# BaseNode.net
KiCad netlist of a schematic drawn in Altium Designer
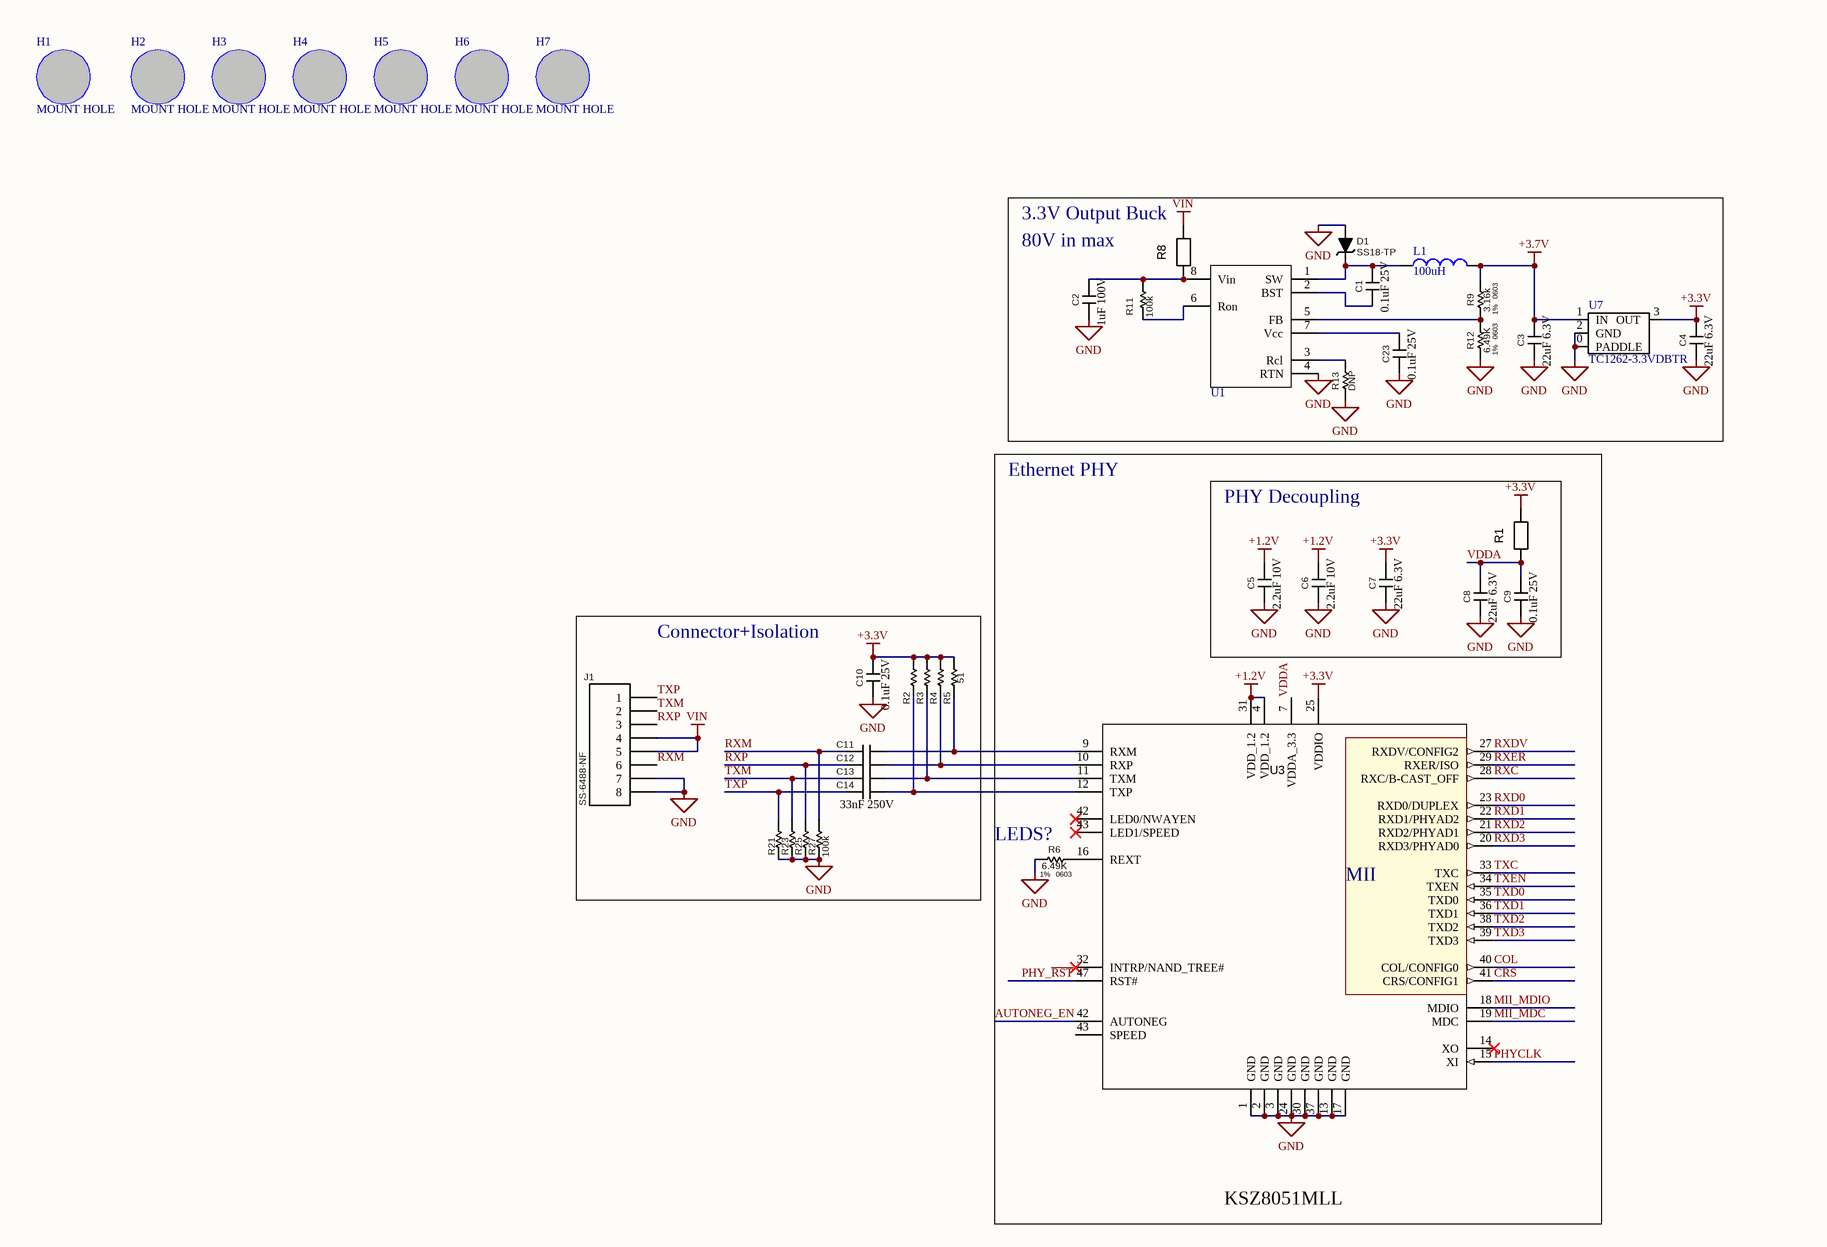
[diagram p0: BaseNode.SchDoc, top left]
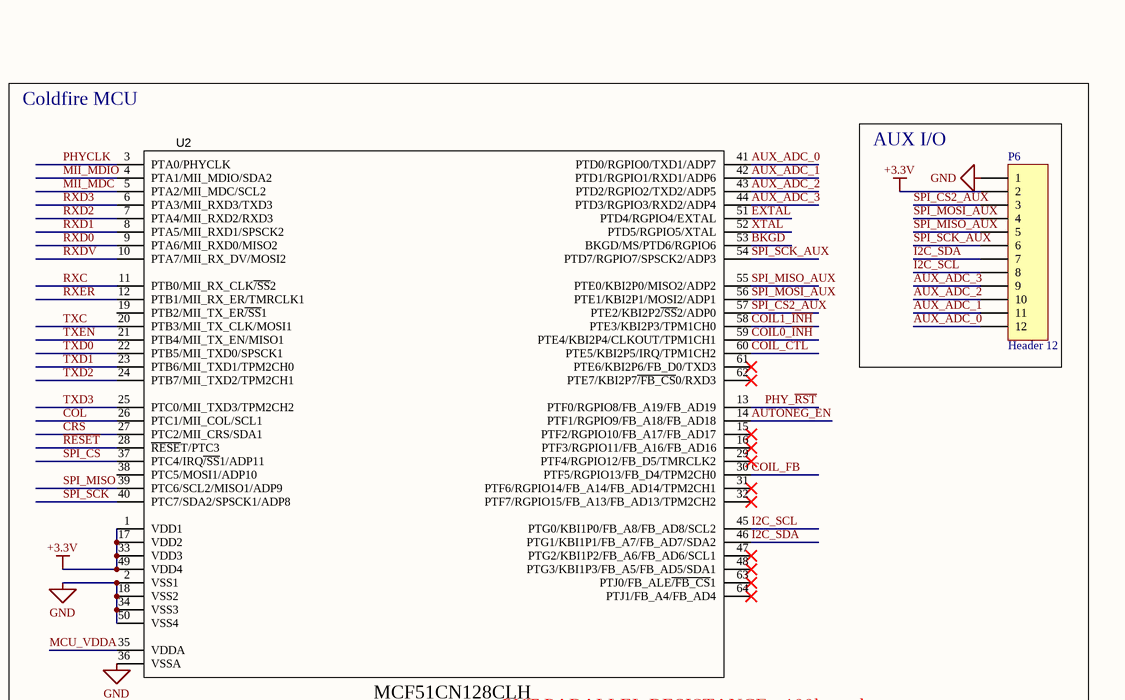
[diagram p1: BaseNode.SchDoc, top right]
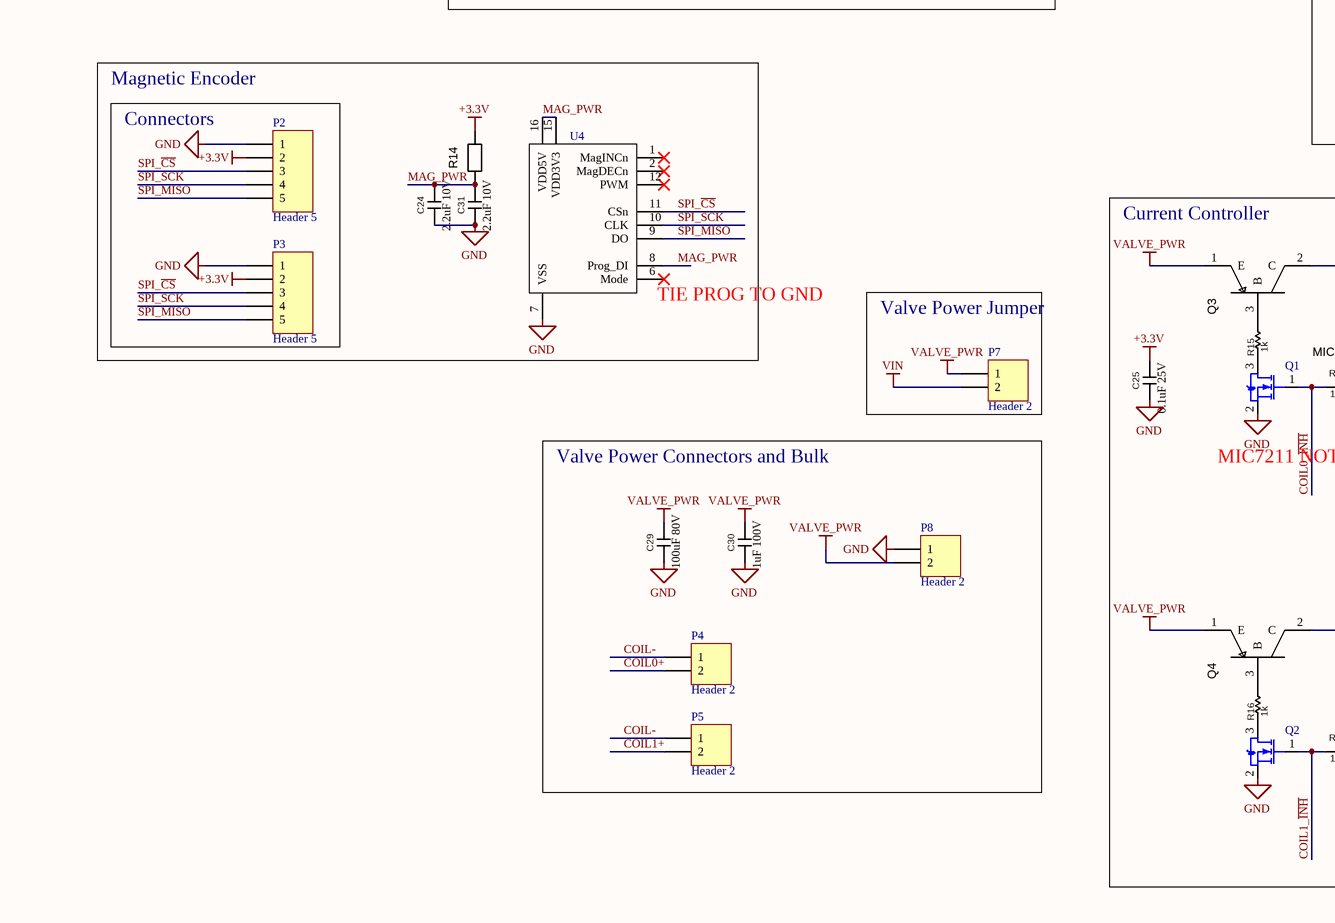
[diagram p2: BaseNode.SchDoc, bottom left]
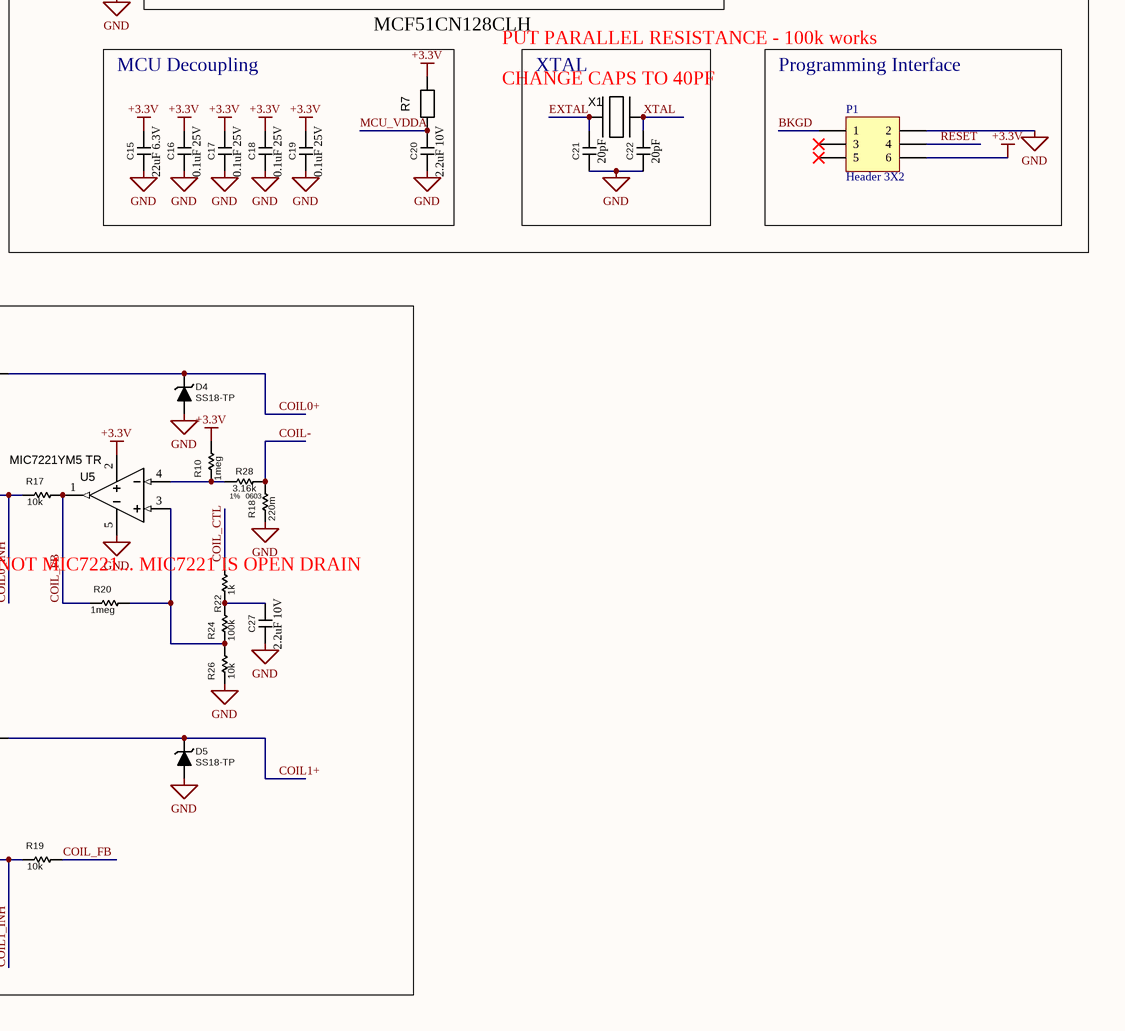
[diagram p3: BaseNode.SchDoc, bottom right]

(export (version "E")
  (design (tool "Eeschema 10.0.6"))
  (components
    (comp (ref "C1")
      (value "0.1uF 25V")
      (footprint "whong:0603")
      (description "Capacitor")
      (fields (field (name "MANUFACTURER") "Murata Electronics North America"))
      (libsource (lib "whong") (part "Capacitor"))
    )
    (comp (ref "C2")
      (value "1uF 100V")
      (footprint "whong:0805")
      (description "Capacitor")
      (fields (field (name "MANUFACTURER") "TDK Corporation"))
      (libsource (lib "whong") (part "Capacitor"))
    )
    (comp (ref "C3")
      (value "22uF 6.3V")
      (footprint "whong:1206")
      (description "Capacitor")
      (fields (field (name "MANUFACTURER") "Taiyo Yuden"))
      (libsource (lib "whong") (part "Capacitor"))
    )
    (comp (ref "C4")
      (value "22uF 6.3V")
      (footprint "whong:1206")
      (description "Capacitor")
      (fields (field (name "MANUFACTURER") "Taiyo Yuden"))
      (libsource (lib "whong") (part "Capacitor"))
    )
    (comp (ref "C5")
      (value "2.2uF 10V")
      (footprint "whong:0603")
      (description "Capacitor")
      (fields (field (name "MANUFACTURER") "Taiyo Yuden"))
      (libsource (lib "whong") (part "Capacitor"))
    )
    (comp (ref "C6")
      (value "2.2uF 10V")
      (footprint "whong:0603")
      (description "Capacitor")
      (fields (field (name "MANUFACTURER") "Taiyo Yuden"))
      (libsource (lib "whong") (part "Capacitor"))
    )
    (comp (ref "C7")
      (value "22uF 6.3V")
      (footprint "whong:1206")
      (description "Capacitor")
      (fields (field (name "MANUFACTURER") "Taiyo Yuden"))
      (libsource (lib "whong") (part "Capacitor"))
    )
    (comp (ref "C8")
      (value "22uF 6.3V")
      (footprint "whong:1206")
      (description "Capacitor")
      (fields (field (name "MANUFACTURER") "Taiyo Yuden"))
      (libsource (lib "whong") (part "Capacitor"))
    )
    (comp (ref "C9")
      (value "0.1uF 25V")
      (footprint "whong:0603")
      (description "Capacitor")
      (fields (field (name "MANUFACTURER") "Murata Electronics North America"))
      (libsource (lib "whong") (part "Capacitor"))
    )
    (comp (ref "C10")
      (value "0.1uF 25V")
      (footprint "whong:0603")
      (description "Capacitor")
      (fields (field (name "MANUFACTURER") "Murata Electronics North America"))
      (libsource (lib "whong") (part "Capacitor"))
    )
    (comp (ref "C11")
      (value "33nF 250V")
      (footprint "whong:0805")
      (description "Capacitor")
      (fields (field (name "MANUFACTURER") "TDK Corporation"))
      (libsource (lib "whong") (part "Capacitor"))
    )
    (comp (ref "C12")
      (value "33nF 250V")
      (footprint "whong:0805")
      (description "Capacitor")
      (fields (field (name "MANUFACTURER") "TDK Corporation"))
      (libsource (lib "whong") (part "Capacitor"))
    )
    (comp (ref "C13")
      (value "33nF 250V")
      (footprint "whong:0805")
      (description "Capacitor")
      (fields (field (name "MANUFACTURER") "TDK Corporation"))
      (libsource (lib "whong") (part "Capacitor"))
    )
    (comp (ref "C14")
      (value "33nF 250V")
      (footprint "whong:0805")
      (description "Capacitor")
      (fields (field (name "MANUFACTURER") "TDK Corporation"))
      (libsource (lib "whong") (part "Capacitor"))
    )
    (comp (ref "C15")
      (value "22uF 6.3V")
      (footprint "whong:1206")
      (description "Capacitor")
      (fields (field (name "MANUFACTURER") "Taiyo Yuden"))
      (libsource (lib "whong") (part "Capacitor"))
    )
    (comp (ref "C16")
      (value "0.1uF 25V")
      (footprint "whong:0603")
      (description "Capacitor")
      (fields (field (name "MANUFACTURER") "Murata Electronics North America"))
      (libsource (lib "whong") (part "Capacitor"))
    )
    (comp (ref "C17")
      (value "0.1uF 25V")
      (footprint "whong:0603")
      (description "Capacitor")
      (fields (field (name "MANUFACTURER") "Murata Electronics North America"))
      (libsource (lib "whong") (part "Capacitor"))
    )
    (comp (ref "C18")
      (value "0.1uF 25V")
      (footprint "whong:0603")
      (description "Capacitor")
      (fields (field (name "MANUFACTURER") "Murata Electronics North America"))
      (libsource (lib "whong") (part "Capacitor"))
    )
    (comp (ref "C19")
      (value "0.1uF 25V")
      (footprint "whong:0603")
      (description "Capacitor")
      (fields (field (name "MANUFACTURER") "Murata Electronics North America"))
      (libsource (lib "whong") (part "Capacitor"))
    )
    (comp (ref "C20")
      (value "2.2uF 10V")
      (footprint "whong:0603")
      (description "Capacitor")
      (fields (field (name "MANUFACTURER") "Taiyo Yuden"))
      (libsource (lib "whong") (part "Capacitor"))
    )
    (comp (ref "C21")
      (value "20pF")
      (footprint "whong:0603")
      (description "Capacitor")
      (fields (field (name "MANUFACTURER") "TDK Corporation"))
      (libsource (lib "whong") (part "Capacitor"))
    )
    (comp (ref "C22")
      (value "20pF")
      (footprint "whong:0603")
      (description "Capacitor")
      (fields (field (name "MANUFACTURER") "TDK Corporation"))
      (libsource (lib "whong") (part "Capacitor"))
    )
    (comp (ref "C23")
      (value "0.1uF 25V")
      (footprint "whong:0603")
      (description "Capacitor")
      (fields (field (name "MANUFACTURER") "Murata Electronics North America"))
      (libsource (lib "whong") (part "Capacitor"))
    )
    (comp (ref "C24")
      (value "2.2uF 10V")
      (footprint "whong:0603")
      (description "Capacitor")
      (fields (field (name "MANUFACTURER") "Taiyo Yuden"))
      (libsource (lib "whong") (part "Capacitor"))
    )
    (comp (ref "C25")
      (value "0.1uF 25V")
      (footprint "whong:0603")
      (description "Capacitor")
      (fields (field (name "MANUFACTURER") "Murata Electronics North America"))
      (libsource (lib "whong") (part "Capacitor"))
    )
    (comp (ref "C27")
      (value "2.2uF 10V")
      (footprint "whong:0603")
      (description "Capacitor")
      (fields (field (name "MANUFACTURER") "Taiyo Yuden"))
      (libsource (lib "whong") (part "Capacitor"))
    )
    (comp (ref "C29")
      (value "100uF 80V")
      (footprint "whong:Capacitor 12mm DIA POLAR")
      (description "Capacitor")
      (fields (field (name "MANUFACTURER") "Panasonic Electronic Components"))
      (libsource (lib "whong") (part "Capacitor"))
    )
    (comp (ref "C30")
      (value "1uF 100V")
      (footprint "whong:0805")
      (description "Capacitor")
      (fields (field (name "MANUFACTURER") "TDK Corporation"))
      (libsource (lib "whong") (part "Capacitor"))
    )
    (comp (ref "C31")
      (value "2.2uF 10V")
      (footprint "whong:0603")
      (description "Capacitor")
      (fields (field (name "MANUFACTURER") "Taiyo Yuden"))
      (libsource (lib "whong") (part "Capacitor"))
    )
    (comp (ref "D1")
      (value "CDBA140-G")
      (footprint "SMA-DIODE")
      (description "DIODE SCHOTTKY 40V 1A SMA")
      (fields (field (name "MANUFACTURER") "Micro Commercial Co") (field (name "MANUFACTURERPN") "SS18-TP"))
      (libsource (lib "whong") (part "CDBA140-G"))
    )
    (comp (ref "D4")
      (value "CDBA140-G")
      (footprint "SMA-DIODE")
      (description "DIODE SCHOTTKY 40V 1A SMA")
      (fields (field (name "MANUFACTURER") "Micro Commercial Co") (field (name "MANUFACTURERPN") "SS18-TP"))
      (libsource (lib "whong") (part "CDBA140-G"))
    )
    (comp (ref "D5")
      (value "CDBA140-G")
      (footprint "SMA-DIODE")
      (description "DIODE SCHOTTKY 40V 1A SMA")
      (fields (field (name "MANUFACTURER") "Micro Commercial Co") (field (name "MANUFACTURERPN") "SS18-TP"))
      (libsource (lib "whong") (part "CDBA140-G"))
    )
    (comp (ref "H1")
      (value "MOUNT HOLE")
      (footprint "MOUNT_HOLE")
      (libsource (lib "whong") (part "MOUNT HOLE"))
    )
    (comp (ref "H2")
      (value "MOUNT HOLE")
      (footprint "MOUNT_HOLE")
      (libsource (lib "whong") (part "MOUNT HOLE"))
    )
    (comp (ref "H3")
      (value "MOUNT HOLE")
      (footprint "MOUNT_HOLE")
      (libsource (lib "whong") (part "MOUNT HOLE"))
    )
    (comp (ref "H4")
      (value "MOUNT HOLE")
      (footprint "MOUNT_HOLE")
      (libsource (lib "whong") (part "MOUNT HOLE"))
    )
    (comp (ref "H5")
      (value "MOUNT HOLE")
      (footprint "MOUNT_HOLE")
      (libsource (lib "whong") (part "MOUNT HOLE"))
    )
    (comp (ref "H6")
      (value "MOUNT HOLE")
      (footprint "MOUNT_HOLE")
      (libsource (lib "whong") (part "MOUNT HOLE"))
    )
    (comp (ref "H7")
      (value "MOUNT HOLE")
      (footprint "MOUNT_HOLE")
      (libsource (lib "whong") (part "MOUNT HOLE"))
    )
    (comp (ref "J1")
      (value "SS-6488-NF")
      (footprint "whong:SS-6488-NF")
      (description "CONN 8-8 MOD JACK")
      (fields (field (name "MANUFACTURER") "Stewart Connector"))
      (libsource (lib "whong") (part "SS-6488-NF"))
    )
    (comp (ref "L1")
      (value "100uH")
      (footprint "whong:NR6028 Inductor")
      (description "Inductor")
      (fields (field (name "MANUFACTURER") "Taiyo Yuden"))
      (libsource (lib "Miscellaneous Devices") (part "Inductor"))
    )
    (comp (ref "P1")
      (value "Header 3X2")
      (footprint "HDR2X3")
      (description "Header, 3-Pin, Dual row")
      (fields (field (name "PUBLISHER") "Altium Limited"))
      (libsource (lib "Miscellaneous Connectors") (part "Header 3X2"))
    )
    (comp (ref "P2")
      (value "Header 5")
      (footprint "HDR1X5")
      (description "Header, 5-Pin")
      (fields (field (name "PUBLISHER") "Altium Limited"))
      (libsource (lib "Miscellaneous Connectors") (part "Header 5"))
    )
    (comp (ref "P3")
      (value "Header 5")
      (footprint "HDR1X5")
      (description "Header, 5-Pin")
      (fields (field (name "PUBLISHER") "Altium Limited"))
      (libsource (lib "Miscellaneous Connectors") (part "Header 5"))
    )
    (comp (ref "P4")
      (value "Header 2")
      (footprint "HDR1X2")
      (description "Header, 2-Pin")
      (fields (field (name "PUBLISHER") "Altium Limited"))
      (libsource (lib "Miscellaneous Connectors") (part "Header 2"))
    )
    (comp (ref "P5")
      (value "Header 2")
      (footprint "HDR1X2")
      (description "Header, 2-Pin")
      (fields (field (name "PUBLISHER") "Altium Limited"))
      (libsource (lib "Miscellaneous Connectors") (part "Header 2"))
    )
    (comp (ref "P6")
      (value "Header 12")
      (footprint "HDR1X12")
      (description "Header, 12-Pin")
      (fields (field (name "PUBLISHER") "Altium Limited"))
      (libsource (lib "Miscellaneous Connectors") (part "Header 12"))
    )
    (comp (ref "P7")
      (value "Header 2")
      (footprint "HDR1X2")
      (description "Header, 2-Pin")
      (fields (field (name "PUBLISHER") "Altium Limited"))
      (libsource (lib "Miscellaneous Connectors") (part "Header 2"))
    )
    (comp (ref "P8")
      (value "Header 2")
      (footprint "HDR1X2")
      (description "Header, 2-Pin")
      (fields (field (name "PUBLISHER") "Altium Limited"))
      (libsource (lib "Miscellaneous Connectors") (part "Header 2"))
    )
    (comp (ref "Q1")
      (value "NFET")
      (footprint "whong:SOT-23")
      (description "FET N-CH 100V 170MA SOT-23")
      (fields (field (name "MANUFACTURER") "Fairchild Semiconductor"))
      (libsource (lib "whong") (part "BSS123"))
    )
    (comp (ref "Q2")
      (value "NFET")
      (footprint "whong:SOT-23")
      (description "FET N-CH 100V 170MA SOT-23")
      (fields (field (name "MANUFACTURER") "Fairchild Semiconductor"))
      (libsource (lib "whong") (part "BSS123"))
    )
    (comp (ref "Q3")
      (value "~")
      (footprint "whong:SOT-89 - PBSS305PX")
      (description "TRANS PNP 80V 4A SOT89")
      (fields (field (name "MANUFACTURER") "NXP Semiconductors"))
      (libsource (lib "whong") (part "PBSS305PX,115"))
    )
    (comp (ref "Q4")
      (value "~")
      (footprint "whong:SOT-89 - PBSS305PX")
      (description "TRANS PNP 80V 4A SOT89")
      (fields (field (name "MANUFACTURER") "NXP Semiconductors"))
      (libsource (lib "whong") (part "PBSS305PX,115"))
    )
    (comp (ref "R1")
      (value "LM4041EIM3X-1.2_1")
      (footprint "whong:0603")
      (description "Ferrite")
      (fields (field (name "MANUFACTURER") "TDK Corporation"))
      (libsource (lib "whong") (part "LM4041EIM3X-1.2_1"))
    )
    (comp (ref "R2")
      (value "51")
      (footprint "whong:0603")
      (description "Resistor")
      (fields (field (name "MANUFACTURER") "Yageo") (field (name "TOLERANCE") "5%"))
      (libsource (lib "whong") (part "Resistor"))
    )
    (comp (ref "R3")
      (value "51")
      (footprint "whong:0603")
      (description "Resistor")
      (fields (field (name "MANUFACTURER") "Yageo") (field (name "TOLERANCE") "5%"))
      (libsource (lib "whong") (part "Resistor"))
    )
    (comp (ref "R4")
      (value "51")
      (footprint "whong:0603")
      (description "Resistor")
      (fields (field (name "MANUFACTURER") "Yageo") (field (name "TOLERANCE") "5%"))
      (libsource (lib "whong") (part "Resistor"))
    )
    (comp (ref "R5")
      (value "51")
      (footprint "whong:0603")
      (description "Resistor")
      (fields (field (name "MANUFACTURER") "Yageo") (field (name "TOLERANCE") "5%"))
      (libsource (lib "whong") (part "Resistor"))
    )
    (comp (ref "R6")
      (value "6.49K")
      (footprint "whong:0603")
      (description "Resistor")
      (fields
        (field (name "MANUFACTURER") "Yageo")
        (field (name "PACKAGE") "0603")
        (field (name "TOLERANCE") "1%")
      )
      (libsource (lib "JamesWhong") (part "Resistor"))
    )
    (comp (ref "R7")
      (value "LM4041EIM3X-1.2_1")
      (footprint "whong:0603")
      (description "Ferrite")
      (fields (field (name "MANUFACTURER") "TDK Corporation"))
      (libsource (lib "whong") (part "LM4041EIM3X-1.2_1"))
    )
    (comp (ref "R8")
      (value "LM4041EIM3X-1.2_1")
      (footprint "whong:0603")
      (description "Ferrite")
      (fields (field (name "MANUFACTURER") "TDK Corporation"))
      (libsource (lib "whong") (part "LM4041EIM3X-1.2_1"))
    )
    (comp (ref "R9")
      (value "3.16k")
      (footprint "whong:0603")
      (description "Resistor")
      (fields
        (field (name "MANUFACTURER") "Yageo")
        (field (name "PACKAGE") "0603")
        (field (name "TOLERANCE") "1%")
      )
      (libsource (lib "JamesWhong") (part "Resistor"))
    )
    (comp (ref "R10")
      (value "1meg")
      (footprint "whong:0603")
      (description "Resistor")
      (fields (field (name "MANUFACTURER") "Yageo") (field (name "TOLERANCE") "5%"))
      (libsource (lib "whong") (part "Resistor"))
    )
    (comp (ref "R11")
      (value "100k")
      (footprint "whong:0603")
      (description "Resistor")
      (fields (field (name "MANUFACTURER") "Yageo"))
      (libsource (lib "whong") (part "Resistor"))
    )
    (comp (ref "R12")
      (value "6.49K")
      (footprint "whong:0603")
      (description "Resistor")
      (fields
        (field (name "MANUFACTURER") "Yageo")
        (field (name "PACKAGE") "0603")
        (field (name "TOLERANCE") "1%")
      )
      (libsource (lib "JamesWhong") (part "Resistor"))
    )
    (comp (ref "R13")
      (value "DNP")
      (footprint "whong:0603")
      (description "Resistor")
      (fields (field (name "TOLERANCE") "1%"))
      (libsource (lib "JamesWhong") (part "Resistor"))
    )
    (comp (ref "R14")
      (value "LM4041EIM3X-1.2_1")
      (footprint "whong:0603")
      (description "Ferrite")
      (fields (field (name "MANUFACTURER") "TDK Corporation"))
      (libsource (lib "whong") (part "LM4041EIM3X-1.2_1"))
    )
    (comp (ref "R15")
      (value "1k")
      (footprint "whong:0603")
      (description "Resistor")
      (fields (field (name "MANUFACTURER") "Yageo") (field (name "TOLERANCE") "5%"))
      (libsource (lib "whong") (part "Resistor"))
    )
    (comp (ref "R16")
      (value "1k")
      (footprint "whong:0603")
      (description "Resistor")
      (fields (field (name "MANUFACTURER") "Yageo") (field (name "TOLERANCE") "5%"))
      (libsource (lib "whong") (part "Resistor"))
    )
    (comp (ref "R17")
      (value "10k")
      (footprint "whong:0603")
      (description "Resistor")
      (fields (field (name "MANUFACTURER") "Yageo"))
      (libsource (lib "whong") (part "Resistor"))
    )
    (comp (ref "R18")
      (value "220m")
      (footprint "whong:0805")
      (description "Resistor")
      (fields (field (name "MANUFACTURER") "Susumu"))
      (libsource (lib "whong") (part "Resistor"))
    )
    (comp (ref "R19")
      (value "10k")
      (footprint "whong:0603")
      (description "Resistor")
      (fields (field (name "MANUFACTURER") "Yageo"))
      (libsource (lib "whong") (part "Resistor"))
    )
    (comp (ref "R20")
      (value "1meg")
      (footprint "whong:0603")
      (description "Resistor")
      (fields (field (name "MANUFACTURER") "Yageo") (field (name "TOLERANCE") "5%"))
      (libsource (lib "whong") (part "Resistor"))
    )
    (comp (ref "R21")
      (value "100k")
      (footprint "whong:0603")
      (description "Resistor")
      (fields (field (name "MANUFACTURER") "Yageo"))
      (libsource (lib "whong") (part "Resistor"))
    )
    (comp (ref "R22")
      (value "1k")
      (footprint "whong:0603")
      (description "Resistor")
      (fields (field (name "MANUFACTURER") "Yageo") (field (name "TOLERANCE") "5%"))
      (libsource (lib "whong") (part "Resistor"))
    )
    (comp (ref "R23")
      (value "100k")
      (footprint "whong:0603")
      (description "Resistor")
      (fields (field (name "MANUFACTURER") "Yageo"))
      (libsource (lib "whong") (part "Resistor"))
    )
    (comp (ref "R24")
      (value "100k")
      (footprint "whong:0603")
      (description "Resistor")
      (fields (field (name "MANUFACTURER") "Yageo"))
      (libsource (lib "whong") (part "Resistor"))
    )
    (comp (ref "R25")
      (value "100k")
      (footprint "whong:0603")
      (description "Resistor")
      (fields (field (name "MANUFACTURER") "Yageo"))
      (libsource (lib "whong") (part "Resistor"))
    )
    (comp (ref "R26")
      (value "10k")
      (footprint "whong:0603")
      (description "Resistor")
      (fields (field (name "MANUFACTURER") "Yageo"))
      (libsource (lib "whong") (part "Resistor"))
    )
    (comp (ref "R27")
      (value "100k")
      (footprint "whong:0603")
      (description "Resistor")
      (fields (field (name "MANUFACTURER") "Yageo"))
      (libsource (lib "whong") (part "Resistor"))
    )
    (comp (ref "R28")
      (value "3.16k")
      (footprint "whong:0603")
      (description "Resistor")
      (fields
        (field (name "MANUFACTURER") "Yageo")
        (field (name "PACKAGE") "0603")
        (field (name "TOLERANCE") "1%")
      )
      (libsource (lib "JamesWhong") (part "Resistor"))
    )
    (comp (ref "U1")
      (value "LM5007MM/NOPB")
      (footprint "whong:MSOP-8")
      (description "BUCK ADJ .5A 8MSOP")
      (fields (field (name "MANUFACTURER") "National Semiconductor"))
      (libsource (lib "whong") (part "LM5007MM/NOPB"))
    )
    (comp (ref "U2")
      (value "MCF51CN128CLH")
      (footprint "LQFP-64 10x10mm .5mm pitch")
      (description "MCU Coldfire w/ Ethernet")
      (fields (field (name "MANUFACTURER") "Freescale Semiconductor"))
      (libsource (lib "whong") (part "MCF51CN128CLH"))
    )
    (comp (ref "U3")
      (value "KSZ8051MLL")
      (footprint "LQFP-48 7x7mm 0.5mm pitch")
      (description "Ethernet PHY MII")
      (fields (field (name "MANUFACTURER") "Micrel Inc"))
      (libsource (lib "whong") (part "KSZ8051MLL"))
    )
    (comp (ref "U4")
      (value "AS5045-ASSU")
      (footprint "whong:SSOP-16")
      (description "IC ENCODER PROG 12-BIT 16-SSOP")
      (fields (field (name "MANUFACTURER") "AMS"))
      (libsource (lib "whong") (part "AS5045-ASSU"))
    )
    (comp (ref "U5")
      (value "MIC7221YM5 TR")
      (footprint "whong:SOT-23-5")
      (description "IC COMPARATOR R-R SOT-23-5")
      (fields (field (name "MANUFACTURER") "Micrel Inc"))
      (libsource (lib "whong") (part "MIC7221YM5 TR"))
    )
    (comp (ref "U7")
      (value "TC1262-3.3VDBTR")
      (footprint "bdilib:SOT-223")
      (description "Regulator IC CMOS LDO 3.3V 500MA SOT223-3")
      (fields
        (field (name "MANUFACTURER") "Microchip Technology")
        (field (name "MANUFACTURERPN") "TC1262-3.3VDBTR")
      )
      (libsource (lib "whong") (part "TC1262-3.3VDBTR"))
    )
    (comp (ref "X1")
      (value "ECS-250-20-3X-EN-TR")
      (footprint "CSM-3X")
      (description "CRYSTAL 25.00000 MHZ 20PF SMD")
      (fields (field (name "MANUFACTURER") "ECS Inc"))
      (libsource (lib "whong") (part "ECS-250-20-3X-EN-TR"))
    )
  )
  (nets
    (net (code "1") (name "+1.2V") (class "Default")
      (node (ref "C5") (pin "2") (pinfunction "2_2") (pintype "passive"))
      (node (ref "C6") (pin "2") (pinfunction "2_2") (pintype "passive"))
      (node (ref "U3") (pin "31") (pinfunction "VDD_1.2_31") (pintype "passive"))
      (node (ref "U3") (pin "4") (pinfunction "VDD_1.2_4") (pintype "passive"))
    )
    (net (code "2") (name "+3.3V") (class "Default")
      (node (ref "C10") (pin "2") (pinfunction "2_2") (pintype "passive"))
      (node (ref "C15") (pin "2") (pinfunction "2_2") (pintype "passive"))
      (node (ref "C16") (pin "2") (pinfunction "2_2") (pintype "passive"))
      (node (ref "C17") (pin "2") (pinfunction "2_2") (pintype "passive"))
      (node (ref "C18") (pin "2") (pinfunction "2_2") (pintype "passive"))
      (node (ref "C19") (pin "2") (pinfunction "2_2") (pintype "passive"))
      (node (ref "C25") (pin "2") (pinfunction "2_2") (pintype "passive"))
      (node (ref "C4") (pin "2") (pinfunction "2_2") (pintype "passive"))
      (node (ref "C7") (pin "2") (pinfunction "2_2") (pintype "passive"))
      (node (ref "P1") (pin "6") (pinfunction "6_6") (pintype "passive"))
      (node (ref "P2") (pin "2") (pinfunction "2_2") (pintype "passive"))
      (node (ref "P3") (pin "2") (pinfunction "2_2") (pintype "passive"))
      (node (ref "P6") (pin "2") (pinfunction "2_2") (pintype "passive"))
      (node (ref "R1") (pin "1") (pinfunction "K_1") (pintype "passive"))
      (node (ref "R10") (pin "2") (pinfunction "2_2") (pintype "passive"))
      (node (ref "R14") (pin "1") (pinfunction "K_1") (pintype "passive"))
      (node (ref "R2") (pin "2") (pinfunction "2_2") (pintype "passive"))
      (node (ref "R3") (pin "2") (pinfunction "2_2") (pintype "passive"))
      (node (ref "R4") (pin "2") (pinfunction "2_2") (pintype "passive"))
      (node (ref "R5") (pin "2") (pinfunction "2_2") (pintype "passive"))
      (node (ref "R7") (pin "1") (pinfunction "K_1") (pintype "passive"))
      (node (ref "U2") (pin "1") (pinfunction "VDD1_1") (pintype "passive"))
      (node (ref "U2") (pin "17") (pinfunction "VDD2_17") (pintype "passive"))
      (node (ref "U2") (pin "33") (pinfunction "VDD3_33") (pintype "passive"))
      (node (ref "U2") (pin "49") (pinfunction "VDD4_49") (pintype "passive"))
      (node (ref "U3") (pin "25") (pinfunction "VDDIO_25") (pintype "passive"))
      (node (ref "U5") (pin "2") (pinfunction "V+_2") (pintype "power_in"))
      (node (ref "U7") (pin "3") (pinfunction "OUT_3") (pintype "passive"))
    )
    (net (code "3") (name "+3.7V") (class "Default")
      (node (ref "C3") (pin "2") (pinfunction "2_2") (pintype "passive"))
      (node (ref "L1") (pin "2") (pinfunction "2_2") (pintype "passive"))
      (node (ref "R9") (pin "2") (pinfunction "2_2") (pintype "passive"))
      (node (ref "U7") (pin "1") (pinfunction "IN_1") (pintype "passive"))
    )
    (net (code "4") (name "/AUTONEG_EN") (class "Default")
      (node (ref "U2") (pin "14") (pinfunction "PTF1/RGPIO9/FB_A18/FB_AD18_14") (pintype "passive"))
      (node (ref "U3") (pin "42") (pinfunction "AUTONEG_42") (pintype "passive"))
    )
    (net (code "5") (name "/AUX_ADC_0") (class "Default")
      (node (ref "P6") (pin "12") (pinfunction "12_12") (pintype "passive"))
      (node (ref "U2") (pin "41") (pinfunction "PTD0/RGPIO0/TXD1/ADP7_41") (pintype "passive"))
    )
    (net (code "6") (name "/AUX_ADC_1") (class "Default")
      (node (ref "P6") (pin "11") (pinfunction "11_11") (pintype "passive"))
      (node (ref "U2") (pin "42") (pinfunction "PTD1/RGPIO1/RXD1/ADP6_42") (pintype "passive"))
    )
    (net (code "7") (name "/AUX_ADC_2") (class "Default")
      (node (ref "P6") (pin "10") (pinfunction "10_10") (pintype "passive"))
      (node (ref "U2") (pin "43") (pinfunction "PTD2/RGPIO2/TXD2/ADP5_43") (pintype "passive"))
    )
    (net (code "8") (name "/AUX_ADC_3") (class "Default")
      (node (ref "P6") (pin "9") (pinfunction "9_9") (pintype "passive"))
      (node (ref "U2") (pin "44") (pinfunction "PTD3/RGPIO3/RXD2/ADP4_44") (pintype "passive"))
    )
    (net (code "9") (name "/BKGD") (class "Default")
      (node (ref "P1") (pin "1") (pinfunction "1_1") (pintype "passive"))
      (node (ref "U2") (pin "53") (pinfunction "BKGD/MS/PTD6/RGPIO6_53") (pintype "passive"))
    )
    (net (code "10") (name "/COIL-") (class "Default")
      (node (ref "P4") (pin "1") (pinfunction "1_1") (pintype "passive"))
      (node (ref "P5") (pin "1") (pinfunction "1_1") (pintype "passive"))
      (node (ref "R18") (pin "2") (pinfunction "2_2") (pintype "passive"))
      (node (ref "R28") (pin "2") (pinfunction "2_2") (pintype "passive"))
    )
    (net (code "11") (name "/COIL0+") (class "Default")
      (node (ref "D4") (pin "K") (pinfunction "K_K") (pintype "passive"))
      (node (ref "P4") (pin "2") (pinfunction "2_2") (pintype "passive"))
      (node (ref "Q3") (pin "2") (pinfunction "C_2") (pintype "passive"))
    )
    (net (code "12") (name "/COIL0_~{INH}") (class "Default")
      (node (ref "Q1") (pin "1") (pinfunction "G_1") (pintype "passive"))
      (node (ref "R17") (pin "1") (pinfunction "1_1") (pintype "passive"))
      (node (ref "U2") (pin "59") (pinfunction "PTE4/KBI2P4/CLKOUT/TPM1CH1_59") (pintype "passive"))
    )
    (net (code "13") (name "/COIL1+") (class "Default")
      (node (ref "D5") (pin "K") (pinfunction "K_K") (pintype "passive"))
      (node (ref "P5") (pin "2") (pinfunction "2_2") (pintype "passive"))
      (node (ref "Q4") (pin "2") (pinfunction "C_2") (pintype "passive"))
    )
    (net (code "14") (name "/COIL1_~{INH}") (class "Default")
      (node (ref "Q2") (pin "1") (pinfunction "G_1") (pintype "passive"))
      (node (ref "R19") (pin "1") (pinfunction "1_1") (pintype "passive"))
      (node (ref "U2") (pin "58") (pinfunction "PTE3/KBI2P3/TPM1CH0_58") (pintype "passive"))
    )
    (net (code "15") (name "/COIL_CTL") (class "Default")
      (node (ref "R22") (pin "2") (pinfunction "2_2") (pintype "passive"))
      (node (ref "U2") (pin "60") (pinfunction "PTE5/KBI2P5/IRQ/TPM1CH2_60") (pintype "passive"))
    )
    (net (code "16") (name "/COIL_FB") (class "Default")
      (node (ref "R17") (pin "2") (pinfunction "2_2") (pintype "passive"))
      (node (ref "R19") (pin "2") (pinfunction "2_2") (pintype "passive"))
      (node (ref "R20") (pin "1") (pinfunction "1_1") (pintype "passive"))
      (node (ref "U2") (pin "30") (pinfunction "PTF5/RGPIO13/FB_D4/TPM2CH0_30") (pintype "passive"))
      (node (ref "U5") (pin "1") (pinfunction "Out_A_1") (pintype "output"))
    )
    (net (code "17") (name "/COL") (class "Default")
      (node (ref "U2") (pin "26") (pinfunction "PTC1/MII_COL/SCL1_26") (pintype "passive"))
      (node (ref "U3") (pin "40") (pinfunction "COL/CONFIG0_40") (pintype "output"))
    )
    (net (code "18") (name "/CRS") (class "Default")
      (node (ref "U2") (pin "27") (pinfunction "PTC2/MII_CRS/SDA1_27") (pintype "passive"))
      (node (ref "U3") (pin "41") (pinfunction "CRS/CONFIG1_41") (pintype "output"))
    )
    (net (code "19") (name "/EXTAL") (class "Default")
      (node (ref "C21") (pin "2") (pinfunction "2_2") (pintype "passive"))
      (node (ref "U2") (pin "51") (pinfunction "PTD4/RGPIO4/EXTAL_51") (pintype "passive"))
      (node (ref "X1") (pin "2") (pinfunction "A_2") (pintype "passive"))
    )
    (net (code "20") (name "/I2C_SCL") (class "Default")
      (node (ref "P6") (pin "8") (pinfunction "8_8") (pintype "passive"))
      (node (ref "U2") (pin "45") (pinfunction "PTG0/KBI1P0/FB_A8/FB_AD8/SCL2_45") (pintype "passive"))
    )
    (net (code "21") (name "/I2C_SDA") (class "Default")
      (node (ref "P6") (pin "7") (pinfunction "7_7") (pintype "passive"))
      (node (ref "U2") (pin "46") (pinfunction "PTG1/KBI1P1/FB_A7/FB_AD7/SDA2_46") (pintype "passive"))
    )
    (net (code "22") (name "/MAG_PWR") (class "Default")
      (node (ref "C24") (pin "2") (pinfunction "2_2") (pintype "passive"))
      (node (ref "C31") (pin "2") (pinfunction "2_2") (pintype "passive"))
      (node (ref "R14") (pin "2") (pinfunction "A_2") (pintype "passive"))
      (node (ref "U4") (pin "15") (pinfunction "VDD3V3_15") (pintype "passive"))
      (node (ref "U4") (pin "16") (pinfunction "VDD5V_16") (pintype "passive"))
      (node (ref "U4") (pin "8") (pinfunction "Prog_DI_8") (pintype "passive"))
    )
    (net (code "23") (name "/MCU_VDDA") (class "Default")
      (node (ref "C20") (pin "2") (pinfunction "2_2") (pintype "passive"))
      (node (ref "R7") (pin "2") (pinfunction "A_2") (pintype "passive"))
      (node (ref "U2") (pin "35") (pinfunction "VDDA_35") (pintype "passive"))
    )
    (net (code "24") (name "/MII_MDC") (class "Default")
      (node (ref "U2") (pin "5") (pinfunction "PTA2/MII_MDC/SCL2_5") (pintype "passive"))
      (node (ref "U3") (pin "19") (pinfunction "MDC_19") (pintype "passive"))
    )
    (net (code "25") (name "/MII_MDIO") (class "Default")
      (node (ref "U2") (pin "4") (pinfunction "PTA1/MII_MDIO/SDA2_4") (pintype "passive"))
      (node (ref "U3") (pin "18") (pinfunction "MDIO_18") (pintype "passive"))
    )
    (net (code "26") (name "/PHYCLK") (class "Default")
      (node (ref "U2") (pin "3") (pinfunction "PTA0/PHYCLK_3") (pintype "passive"))
      (node (ref "U3") (pin "15") (pinfunction "XI_15") (pintype "input"))
    )
    (net (code "27") (name "/PHY_~{RST}") (class "Default")
      (node (ref "U2") (pin "13") (pinfunction "PTF0/RGPIO8/FB_A19/FB_AD19_13") (pintype "passive"))
      (node (ref "U3") (pin "47") (pinfunction "RST#_47") (pintype "passive"))
    )
    (net (code "28") (name "/RXC") (class "Default")
      (node (ref "U2") (pin "11") (pinfunction "PTB0/MII_RX_CLK~{/SS}2_11") (pintype "passive"))
      (node (ref "U3") (pin "28") (pinfunction "RXC/B-CAST_OFF_28") (pintype "output"))
    )
    (net (code "29") (name "/RXD0") (class "Default")
      (node (ref "U2") (pin "9") (pinfunction "PTA6/MII_RXD0/MISO2_9") (pintype "passive"))
      (node (ref "U3") (pin "23") (pinfunction "RXD0/DUPLEX_23") (pintype "output"))
    )
    (net (code "30") (name "/RXD1") (class "Default")
      (node (ref "U2") (pin "8") (pinfunction "PTA5/MII_RXD1/SPSCK2_8") (pintype "passive"))
      (node (ref "U3") (pin "22") (pinfunction "RXD1/PHYAD2_22") (pintype "output"))
    )
    (net (code "31") (name "/RXD2") (class "Default")
      (node (ref "U2") (pin "7") (pinfunction "PTA4/MII_RXD2/RXD3_7") (pintype "passive"))
      (node (ref "U3") (pin "21") (pinfunction "RXD2/PHYAD1_21") (pintype "output"))
    )
    (net (code "32") (name "/RXD3") (class "Default")
      (node (ref "U2") (pin "6") (pinfunction "PTA3/MII_RXD3/TXD3_6") (pintype "passive"))
      (node (ref "U3") (pin "20") (pinfunction "RXD3/PHYAD0_20") (pintype "output"))
    )
    (net (code "33") (name "/RXDV") (class "Default")
      (node (ref "U2") (pin "10") (pinfunction "PTA7/MII_RX_DV/MOSI2_10") (pintype "passive"))
      (node (ref "U3") (pin "27") (pinfunction "RXDV/CONFIG2_27") (pintype "output"))
    )
    (net (code "34") (name "/RXER") (class "Default")
      (node (ref "U2") (pin "12") (pinfunction "PTB1/MII_RX_ER/TMRCLK1_12") (pintype "passive"))
      (node (ref "U3") (pin "29") (pinfunction "RXER/ISO_29") (pintype "output"))
    )
    (net (code "35") (name "/RXM") (class "Default")
      (node (ref "C11") (pin "1") (pinfunction "1_1") (pintype "passive"))
      (node (ref "J1") (pin "6") (pinfunction "6_6") (pintype "passive"))
      (node (ref "R27") (pin "2") (pinfunction "2_2") (pintype "passive"))
    )
    (net (code "36") (name "/RXP") (class "Default")
      (node (ref "C12") (pin "1") (pinfunction "1_1") (pintype "passive"))
      (node (ref "J1") (pin "3") (pinfunction "3_3") (pintype "passive"))
      (node (ref "R25") (pin "2") (pinfunction "2_2") (pintype "passive"))
    )
    (net (code "37") (name "/SPI_MISO") (class "Default")
      (node (ref "P2") (pin "5") (pinfunction "5_5") (pintype "passive"))
      (node (ref "P3") (pin "5") (pinfunction "5_5") (pintype "passive"))
      (node (ref "U2") (pin "39") (pinfunction "PTC6/SCL2/MISO1/ADP9_39") (pintype "passive"))
      (node (ref "U4") (pin "9") (pinfunction "DO_9") (pintype "passive"))
    )
    (net (code "38") (name "/SPI_MISO_AUX") (class "Default")
      (node (ref "P6") (pin "5") (pinfunction "5_5") (pintype "passive"))
      (node (ref "U2") (pin "55") (pinfunction "PTE0/KBI2P0/MISO2/ADP2_55") (pintype "passive"))
    )
    (net (code "39") (name "/SPI_MOSI_AUX") (class "Default")
      (node (ref "P6") (pin "4") (pinfunction "4_4") (pintype "passive"))
      (node (ref "U2") (pin "56") (pinfunction "PTE1/KBI2P1/MOSI2/ADP1_56") (pintype "passive"))
    )
    (net (code "40") (name "/SPI_SCK") (class "Default")
      (node (ref "P2") (pin "4") (pinfunction "4_4") (pintype "passive"))
      (node (ref "P3") (pin "4") (pinfunction "4_4") (pintype "passive"))
      (node (ref "U2") (pin "40") (pinfunction "PTC7/SDA2/SPSCK1/ADP8_40") (pintype "passive"))
      (node (ref "U4") (pin "10") (pinfunction "CLK_10") (pintype "passive"))
    )
    (net (code "41") (name "/SPI_SCK_AUX") (class "Default")
      (node (ref "P6") (pin "6") (pinfunction "6_6") (pintype "passive"))
      (node (ref "U2") (pin "54") (pinfunction "PTD7/RGPIO7/SPSCK2/ADP3_54") (pintype "passive"))
    )
    (net (code "42") (name "/SPI_~{CS2}_AUX") (class "Default")
      (node (ref "P6") (pin "3") (pinfunction "3_3") (pintype "passive"))
      (node (ref "U2") (pin "57") (pinfunction "PTE2/KBI2P2~{/SS}2/ADP0_57") (pintype "passive"))
    )
    (net (code "43") (name "/SPI_~{CS}") (class "Default")
      (node (ref "P2") (pin "3") (pinfunction "3_3") (pintype "passive"))
      (node (ref "P3") (pin "3") (pinfunction "3_3") (pintype "passive"))
      (node (ref "U2") (pin "37") (pinfunction "PTC4/IRQ~{/SS}1/ADP11_37") (pintype "passive"))
      (node (ref "U4") (pin "11") (pinfunction "CSn_11") (pintype "passive"))
    )
    (net (code "44") (name "/TXC") (class "Default")
      (node (ref "U2") (pin "20") (pinfunction "PTB3/MII_TX_CLK/MOSI1_20") (pintype "passive"))
      (node (ref "U3") (pin "33") (pinfunction "TXC_33") (pintype "output"))
    )
    (net (code "45") (name "/TXD0") (class "Default")
      (node (ref "U2") (pin "22") (pinfunction "PTB5/MII_TXD0/SPSCK1_22") (pintype "passive"))
      (node (ref "U3") (pin "35") (pinfunction "TXD0_35") (pintype "input"))
    )
    (net (code "46") (name "/TXD1") (class "Default")
      (node (ref "U2") (pin "23") (pinfunction "PTB6/MII_TXD1/TPM2CH0_23") (pintype "passive"))
      (node (ref "U3") (pin "36") (pinfunction "TXD1_36") (pintype "input"))
    )
    (net (code "47") (name "/TXD2") (class "Default")
      (node (ref "U2") (pin "24") (pinfunction "PTB7/MII_TXD2/TPM2CH1_24") (pintype "passive"))
      (node (ref "U3") (pin "38") (pinfunction "TXD2_38") (pintype "input"))
    )
    (net (code "48") (name "/TXD3") (class "Default")
      (node (ref "U2") (pin "25") (pinfunction "PTC0/MII_TXD3/TPM2CH2_25") (pintype "passive"))
      (node (ref "U3") (pin "39") (pinfunction "TXD3_39") (pintype "input"))
    )
    (net (code "49") (name "/TXEN") (class "Default")
      (node (ref "U2") (pin "21") (pinfunction "PTB4/MII_TX_EN/MISO1_21") (pintype "passive"))
      (node (ref "U3") (pin "34") (pinfunction "TXEN_34") (pintype "input"))
    )
    (net (code "50") (name "/TXM") (class "Default")
      (node (ref "C13") (pin "1") (pinfunction "1_1") (pintype "passive"))
      (node (ref "J1") (pin "2") (pinfunction "2_2") (pintype "passive"))
      (node (ref "R23") (pin "2") (pinfunction "2_2") (pintype "passive"))
    )
    (net (code "51") (name "/TXP") (class "Default")
      (node (ref "C14") (pin "1") (pinfunction "1_1") (pintype "passive"))
      (node (ref "J1") (pin "1") (pinfunction "1_1") (pintype "passive"))
      (node (ref "R21") (pin "2") (pinfunction "2_2") (pintype "passive"))
    )
    (net (code "52") (name "/VDDA") (class "Default")
      (node (ref "C8") (pin "2") (pinfunction "2_2") (pintype "passive"))
      (node (ref "C9") (pin "2") (pinfunction "2_2") (pintype "passive"))
      (node (ref "R1") (pin "2") (pinfunction "A_2") (pintype "passive"))
      (node (ref "U3") (pin "7") (pinfunction "VDDA_3.3_7") (pintype "passive"))
    )
    (net (code "53") (name "/XTAL") (class "Default")
      (node (ref "C22") (pin "2") (pinfunction "2_2") (pintype "passive"))
      (node (ref "U2") (pin "52") (pinfunction "PTD5/RGPIO5/XTAL_52") (pintype "passive"))
      (node (ref "X1") (pin "1") (pinfunction "K_1") (pintype "passive"))
    )
    (net (code "54") (name "/~{RESET}") (class "Default")
      (node (ref "P1") (pin "4") (pinfunction "4_4") (pintype "passive"))
      (node (ref "U2") (pin "28") (pinfunction "~{RESE}T/PTC3_28") (pintype "passive"))
    )
    (net (code "55") (name "GND") (class "Default")
      (node (ref "C10") (pin "1") (pinfunction "1_1") (pintype "passive"))
      (node (ref "C15") (pin "1") (pinfunction "1_1") (pintype "passive"))
      (node (ref "C16") (pin "1") (pinfunction "1_1") (pintype "passive"))
      (node (ref "C17") (pin "1") (pinfunction "1_1") (pintype "passive"))
      (node (ref "C18") (pin "1") (pinfunction "1_1") (pintype "passive"))
      (node (ref "C19") (pin "1") (pinfunction "1_1") (pintype "passive"))
      (node (ref "C2") (pin "1") (pinfunction "1_1") (pintype "passive"))
      (node (ref "C20") (pin "1") (pinfunction "1_1") (pintype "passive"))
      (node (ref "C21") (pin "1") (pinfunction "1_1") (pintype "passive"))
      (node (ref "C22") (pin "1") (pinfunction "1_1") (pintype "passive"))
      (node (ref "C23") (pin "1") (pinfunction "1_1") (pintype "passive"))
      (node (ref "C24") (pin "1") (pinfunction "1_1") (pintype "passive"))
      (node (ref "C25") (pin "1") (pinfunction "1_1") (pintype "passive"))
      (node (ref "C27") (pin "1") (pinfunction "1_1") (pintype "passive"))
      (node (ref "C29") (pin "1") (pinfunction "1_1") (pintype "passive"))
      (node (ref "C3") (pin "1") (pinfunction "1_1") (pintype "passive"))
      (node (ref "C30") (pin "1") (pinfunction "1_1") (pintype "passive"))
      (node (ref "C31") (pin "1") (pinfunction "1_1") (pintype "passive"))
      (node (ref "C4") (pin "1") (pinfunction "1_1") (pintype "passive"))
      (node (ref "C5") (pin "1") (pinfunction "1_1") (pintype "passive"))
      (node (ref "C6") (pin "1") (pinfunction "1_1") (pintype "passive"))
      (node (ref "C7") (pin "1") (pinfunction "1_1") (pintype "passive"))
      (node (ref "C8") (pin "1") (pinfunction "1_1") (pintype "passive"))
      (node (ref "C9") (pin "1") (pinfunction "1_1") (pintype "passive"))
      (node (ref "D1") (pin "A") (pinfunction "A_A") (pintype "passive"))
      (node (ref "D4") (pin "A") (pinfunction "A_A") (pintype "passive"))
      (node (ref "D5") (pin "A") (pinfunction "A_A") (pintype "passive"))
      (node (ref "J1") (pin "7") (pinfunction "7_7") (pintype "passive"))
      (node (ref "J1") (pin "8") (pinfunction "8_8") (pintype "passive"))
      (node (ref "P1") (pin "2") (pinfunction "2_2") (pintype "passive"))
      (node (ref "P2") (pin "1") (pinfunction "1_1") (pintype "passive"))
      (node (ref "P3") (pin "1") (pinfunction "1_1") (pintype "passive"))
      (node (ref "P6") (pin "1") (pinfunction "1_1") (pintype "passive"))
      (node (ref "P8") (pin "1") (pinfunction "1_1") (pintype "passive"))
      (node (ref "Q1") (pin "2") (pintype "passive"))
      (node (ref "Q2") (pin "2") (pintype "passive"))
      (node (ref "R12") (pin "1") (pinfunction "1_1") (pintype "passive"))
      (node (ref "R13") (pin "1") (pinfunction "1_1") (pintype "passive"))
      (node (ref "R18") (pin "1") (pinfunction "1_1") (pintype "passive"))
      (node (ref "R21") (pin "1") (pinfunction "1_1") (pintype "passive"))
      (node (ref "R23") (pin "1") (pinfunction "1_1") (pintype "passive"))
      (node (ref "R25") (pin "1") (pinfunction "1_1") (pintype "passive"))
      (node (ref "R26") (pin "1") (pinfunction "1_1") (pintype "passive"))
      (node (ref "R27") (pin "1") (pinfunction "1_1") (pintype "passive"))
      (node (ref "R6") (pin "1") (pinfunction "1_1") (pintype "passive"))
      (node (ref "U1") (pin "4") (pinfunction "RTN_4") (pintype "passive"))
      (node (ref "U2") (pin "18") (pinfunction "VSS2_18") (pintype "passive"))
      (node (ref "U2") (pin "2") (pinfunction "VSS1_2") (pintype "passive"))
      (node (ref "U2") (pin "34") (pinfunction "VSS3_34") (pintype "passive"))
      (node (ref "U2") (pin "36") (pinfunction "VSSA_36") (pintype "passive"))
      (node (ref "U2") (pin "50") (pinfunction "VSS4_50") (pintype "passive"))
      (node (ref "U3") (pin "1") (pinfunction "GND_1") (pintype "passive"))
      (node (ref "U3") (pin "13") (pinfunction "GND_13") (pintype "passive"))
      (node (ref "U3") (pin "17") (pinfunction "GND_17") (pintype "passive"))
      (node (ref "U3") (pin "2") (pinfunction "GND_2") (pintype "passive"))
      (node (ref "U3") (pin "24") (pinfunction "GND_24") (pintype "passive"))
      (node (ref "U3") (pin "3") (pinfunction "GND_3") (pintype "passive"))
      (node (ref "U3") (pin "30") (pinfunction "GND_30") (pintype "passive"))
      (node (ref "U3") (pin "37") (pinfunction "GND_37") (pintype "passive"))
      (node (ref "U4") (pin "7") (pinfunction "VSS_7") (pintype "passive"))
      (node (ref "U5") (pin "5") (pinfunction "V-_5") (pintype "power_in"))
      (node (ref "U7") (pin "0") (pinfunction "PADDLE_0") (pintype "passive"))
      (node (ref "U7") (pin "2") (pinfunction "GND_2") (pintype "passive"))
    )
    (net (code "56") (name "Net-(C27-Pad2)") (class "Default")
      (node (ref "C27") (pin "2") (pinfunction "2_2") (pintype "passive"))
      (node (ref "R22") (pin "1") (pinfunction "1_1") (pintype "passive"))
      (node (ref "R24") (pin "2") (pinfunction "2_2") (pintype "passive"))
    )
    (net (code "57") (name "Net-(Q1-Pad3)") (class "Default")
      (node (ref "Q1") (pin "3") (pintype "passive"))
      (node (ref "R15") (pin "1") (pinfunction "1_1") (pintype "passive"))
    )
    (net (code "58") (name "Net-(Q2-Pad3)") (class "Default")
      (node (ref "Q2") (pin "3") (pintype "passive"))
      (node (ref "R16") (pin "1") (pinfunction "1_1") (pintype "passive"))
    )
    (net (code "59") (name "Net-(Q3-B)") (class "Default")
      (node (ref "Q3") (pin "3") (pinfunction "B_3") (pintype "passive"))
      (node (ref "R15") (pin "2") (pinfunction "2_2") (pintype "passive"))
    )
    (net (code "60") (name "Net-(Q4-B)") (class "Default")
      (node (ref "Q4") (pin "3") (pinfunction "B_3") (pintype "passive"))
      (node (ref "R16") (pin "2") (pinfunction "2_2") (pintype "passive"))
    )
    (net (code "61") (name "Net-(R8-A)") (class "Default")
      (node (ref "C2") (pin "2") (pinfunction "2_2") (pintype "passive"))
      (node (ref "R11") (pin "2") (pinfunction "2_2") (pintype "passive"))
      (node (ref "R8") (pin "2") (pinfunction "A_2") (pintype "passive"))
      (node (ref "U1") (pin "8") (pinfunction "Vin_8") (pintype "passive"))
    )
    (net (code "62") (name "Net-(U1-BST)") (class "Default")
      (node (ref "C1") (pin "1") (pinfunction "1_1") (pintype "passive"))
      (node (ref "U1") (pin "2") (pinfunction "BST_2") (pintype "passive"))
    )
    (net (code "63") (name "Net-(U1-FB)") (class "Default")
      (node (ref "R12") (pin "2") (pinfunction "2_2") (pintype "passive"))
      (node (ref "R9") (pin "1") (pinfunction "1_1") (pintype "passive"))
      (node (ref "U1") (pin "5") (pinfunction "FB_5") (pintype "passive"))
    )
    (net (code "64") (name "Net-(U1-Rcl)") (class "Default")
      (node (ref "R13") (pin "2") (pinfunction "2_2") (pintype "passive"))
      (node (ref "U1") (pin "3") (pinfunction "Rcl_3") (pintype "passive"))
    )
    (net (code "65") (name "Net-(U1-Ron)") (class "Default")
      (node (ref "R11") (pin "1") (pinfunction "1_1") (pintype "passive"))
      (node (ref "U1") (pin "6") (pinfunction "Ron_6") (pintype "passive"))
    )
    (net (code "66") (name "Net-(U1-SW)") (class "Default")
      (node (ref "C1") (pin "2") (pinfunction "2_2") (pintype "passive"))
      (node (ref "D1") (pin "K") (pinfunction "K_K") (pintype "passive"))
      (node (ref "L1") (pin "1") (pinfunction "1_1") (pintype "passive"))
      (node (ref "U1") (pin "1") (pinfunction "SW_1") (pintype "passive"))
    )
    (net (code "67") (name "Net-(U1-Vcc)") (class "Default")
      (node (ref "C23") (pin "2") (pinfunction "2_2") (pintype "passive"))
      (node (ref "U1") (pin "7") (pinfunction "Vcc_7") (pintype "passive"))
    )
    (net (code "68") (name "Net-(U3-REXT)") (class "Default")
      (node (ref "R6") (pin "2") (pinfunction "2_2") (pintype "passive"))
      (node (ref "U3") (pin "16") (pinfunction "REXT_16") (pintype "passive"))
    )
    (net (code "69") (name "Net-(U3-RXM)") (class "Default")
      (node (ref "C11") (pin "2") (pinfunction "2_2") (pintype "passive"))
      (node (ref "R5") (pin "1") (pinfunction "1_1") (pintype "passive"))
      (node (ref "U3") (pin "9") (pinfunction "RXM_9") (pintype "passive"))
    )
    (net (code "70") (name "Net-(U3-RXP)") (class "Default")
      (node (ref "C12") (pin "2") (pinfunction "2_2") (pintype "passive"))
      (node (ref "R4") (pin "1") (pinfunction "1_1") (pintype "passive"))
      (node (ref "U3") (pin "10") (pinfunction "RXP_10") (pintype "passive"))
    )
    (net (code "71") (name "Net-(U3-TXM)") (class "Default")
      (node (ref "C13") (pin "2") (pinfunction "2_2") (pintype "passive"))
      (node (ref "R3") (pin "1") (pinfunction "1_1") (pintype "passive"))
      (node (ref "U3") (pin "11") (pinfunction "TXM_11") (pintype "passive"))
    )
    (net (code "72") (name "Net-(U3-TXP)") (class "Default")
      (node (ref "C14") (pin "2") (pinfunction "2_2") (pintype "passive"))
      (node (ref "R2") (pin "1") (pinfunction "1_1") (pintype "passive"))
      (node (ref "U3") (pin "12") (pinfunction "TXP_12") (pintype "passive"))
    )
    (net (code "73") (name "Net-(U5-IN+_A)") (class "Default")
      (node (ref "R20") (pin "2") (pinfunction "2_2") (pintype "passive"))
      (node (ref "R24") (pin "1") (pinfunction "1_1") (pintype "passive"))
      (node (ref "R26") (pin "2") (pinfunction "2_2") (pintype "passive"))
      (node (ref "U5") (pin "3") (pinfunction "IN+_A_3") (pintype "input"))
    )
    (net (code "74") (name "Net-(U5-IN-_A)") (class "Default")
      (node (ref "R10") (pin "1") (pinfunction "1_1") (pintype "passive"))
      (node (ref "R28") (pin "1") (pinfunction "1_1") (pintype "passive"))
      (node (ref "U5") (pin "4") (pinfunction "IN-_A_4") (pintype "input"))
    )
    (net (code "75") (name "VALVE_PWR") (class "Default")
      (node (ref "C29") (pin "2") (pinfunction "2_2") (pintype "passive"))
      (node (ref "C30") (pin "2") (pinfunction "2_2") (pintype "passive"))
      (node (ref "P7") (pin "1") (pinfunction "1_1") (pintype "passive"))
      (node (ref "P8") (pin "2") (pinfunction "2_2") (pintype "passive"))
      (node (ref "Q3") (pin "1") (pinfunction "E_1") (pintype "passive"))
      (node (ref "Q4") (pin "1") (pinfunction "E_1") (pintype "passive"))
    )
    (net (code "76") (name "VIN") (class "Default")
      (node (ref "J1") (pin "4") (pinfunction "4_4") (pintype "passive"))
      (node (ref "J1") (pin "5") (pinfunction "5_5") (pintype "passive"))
      (node (ref "P7") (pin "2") (pinfunction "2_2") (pintype "passive"))
      (node (ref "R8") (pin "1") (pinfunction "K_1") (pintype "passive"))
    )
    (net (code "77") (name "unconnected-(P1-Pad3)") (class "Default")
      (node (ref "P1") (pin "3") (pinfunction "3_3") (pintype "passive+no_connect"))
    )
    (net (code "78") (name "unconnected-(P1-Pad5)") (class "Default")
      (node (ref "P1") (pin "5") (pinfunction "5_5") (pintype "passive+no_connect"))
    )
    (net (code "79") (name "unconnected-(U2-PTB2{slash}MII_TX_ER~{{slash}SS}1-Pad19)") (class "Default")
      (node (ref "U2") (pin "19") (pinfunction "PTB2/MII_TX_ER~{/SS}1_19") (pintype "passive"))
    )
    (net (code "80") (name "unconnected-(U2-PTC5{slash}MOSI1{slash}ADP10-Pad38)") (class "Default")
      (node (ref "U2") (pin "38") (pinfunction "PTC5/MOSI1/ADP10_38") (pintype "passive"))
    )
    (net (code "81") (name "unconnected-(U2-PTE6{slash}KBI2P6{slash}FB_D0{slash}TXD3-Pad61)") (class "Default")
      (node (ref "U2") (pin "61") (pinfunction "PTE6/KBI2P6/FB_D0/TXD3_61") (pintype "passive+no_connect"))
    )
    (net (code "82") (name "unconnected-(U2-PTE7{slash}KBI2P7~{{slash}FB_CS}0{slash}RXD3-Pad62)") (class "Default")
      (node (ref "U2") (pin "62") (pinfunction "PTE7/KBI2P7~{/FB_CS}0/RXD3_62") (pintype "passive+no_connect"))
    )
    (net (code "83") (name "unconnected-(U2-PTF2{slash}RGPIO10{slash}FB_A17{slash}FB_AD17-Pad15)") (class "Default")
      (node (ref "U2") (pin "15") (pinfunction "PTF2/RGPIO10/FB_A17/FB_AD17_15") (pintype "passive+no_connect"))
    )
    (net (code "84") (name "unconnected-(U2-PTF3{slash}RGPIO11{slash}FB_A16{slash}FB_AD16-Pad16)") (class "Default")
      (node (ref "U2") (pin "16") (pinfunction "PTF3/RGPIO11/FB_A16/FB_AD16_16") (pintype "passive+no_connect"))
    )
    (net (code "85") (name "unconnected-(U2-PTF4{slash}RGPIO12{slash}FB_D5{slash}TMRCLK2-Pad29)") (class "Default")
      (node (ref "U2") (pin "29") (pinfunction "PTF4/RGPIO12/FB_D5/TMRCLK2_29") (pintype "passive+no_connect"))
    )
    (net (code "86") (name "unconnected-(U2-PTF6{slash}RGPIO14{slash}FB_A14{slash}FB_AD14{slash}TPM2CH1-Pad31)") (class "Default")
      (node (ref "U2") (pin "31") (pinfunction "PTF6/RGPIO14/FB_A14/FB_AD14/TPM2CH1_31") (pintype "passive+no_connect"))
    )
    (net (code "87") (name "unconnected-(U2-PTF7{slash}RGPIO15{slash}FB_A13{slash}FB_AD13{slash}TPM2CH2-Pad32)") (class "Default")
      (node (ref "U2") (pin "32") (pinfunction "PTF7/RGPIO15/FB_A13/FB_AD13/TPM2CH2_32") (pintype "passive+no_connect"))
    )
    (net (code "88") (name "unconnected-(U2-PTG2{slash}KBI1P2{slash}FB_A6{slash}FB_AD6{slash}SCL1-Pad47)") (class "Default")
      (node (ref "U2") (pin "47") (pinfunction "PTG2/KBI1P2/FB_A6/FB_AD6/SCL1_47") (pintype "passive+no_connect"))
    )
    (net (code "89") (name "unconnected-(U2-PTG3{slash}KBI1P3{slash}FB_A5{slash}FB_AD5{slash}SDA1-Pad48)") (class "Default")
      (node (ref "U2") (pin "48") (pinfunction "PTG3/KBI1P3/FB_A5/FB_AD5/SDA1_48") (pintype "passive+no_connect"))
    )
    (net (code "90") (name "unconnected-(U2-PTJ0{slash}FB_ALE~{{slash}FB_CS}1-Pad63)") (class "Default")
      (node (ref "U2") (pin "63") (pinfunction "PTJ0/FB_ALE~{/FB_CS}1_63") (pintype "passive+no_connect"))
    )
    (net (code "91") (name "unconnected-(U2-PTJ1{slash}FB_A4{slash}FB_AD4-Pad64)") (class "Default")
      (node (ref "U2") (pin "64") (pinfunction "PTJ1/FB_A4/FB_AD4_64") (pintype "passive+no_connect"))
    )
    (net (code "92") (name "unconnected-(U3-INTRP{slash}NAND_TREE#-Pad32)") (class "Default")
      (node (ref "U3") (pin "32") (pinfunction "INTRP/NAND_TREE#_32") (pintype "passive+no_connect"))
    )
    (net (code "93") (name "unconnected-(U3-LED0{slash}NWAYEN-Pad42)") (class "Default")
      (node (ref "U3") (pin "42") (pinfunction "LED0/NWAYEN_42") (pintype "passive+no_connect"))
    )
    (net (code "94") (name "unconnected-(U3-LED1{slash}SPEED-Pad43)") (class "Default")
      (node (ref "U3") (pin "43") (pinfunction "LED1/SPEED_43") (pintype "passive+no_connect"))
    )
    (net (code "95") (name "unconnected-(U3-SPEED-Pad43)") (class "Default")
      (node (ref "U3") (pin "43") (pinfunction "SPEED_43") (pintype "passive"))
    )
    (net (code "96") (name "unconnected-(U3-XO-Pad14)") (class "Default")
      (node (ref "U3") (pin "14") (pinfunction "XO_14") (pintype "passive+no_connect"))
    )
    (net (code "97") (name "unconnected-(U4-MagDECn-Pad2)") (class "Default")
      (node (ref "U4") (pin "2") (pinfunction "MagDECn_2") (pintype "passive+no_connect"))
    )
    (net (code "98") (name "unconnected-(U4-MagINCn-Pad1)") (class "Default")
      (node (ref "U4") (pin "1") (pinfunction "MagINCn_1") (pintype "passive+no_connect"))
    )
    (net (code "99") (name "unconnected-(U4-Mode-Pad6)") (class "Default")
      (node (ref "U4") (pin "6") (pinfunction "Mode_6") (pintype "passive+no_connect"))
    )
    (net (code "100") (name "unconnected-(U4-PWM-Pad12)") (class "Default")
      (node (ref "U4") (pin "12") (pinfunction "PWM_12") (pintype "passive+no_connect"))
    )
  )
)
